# old_main_board.net
KiCad netlist of a schematic drawn in EAGLE
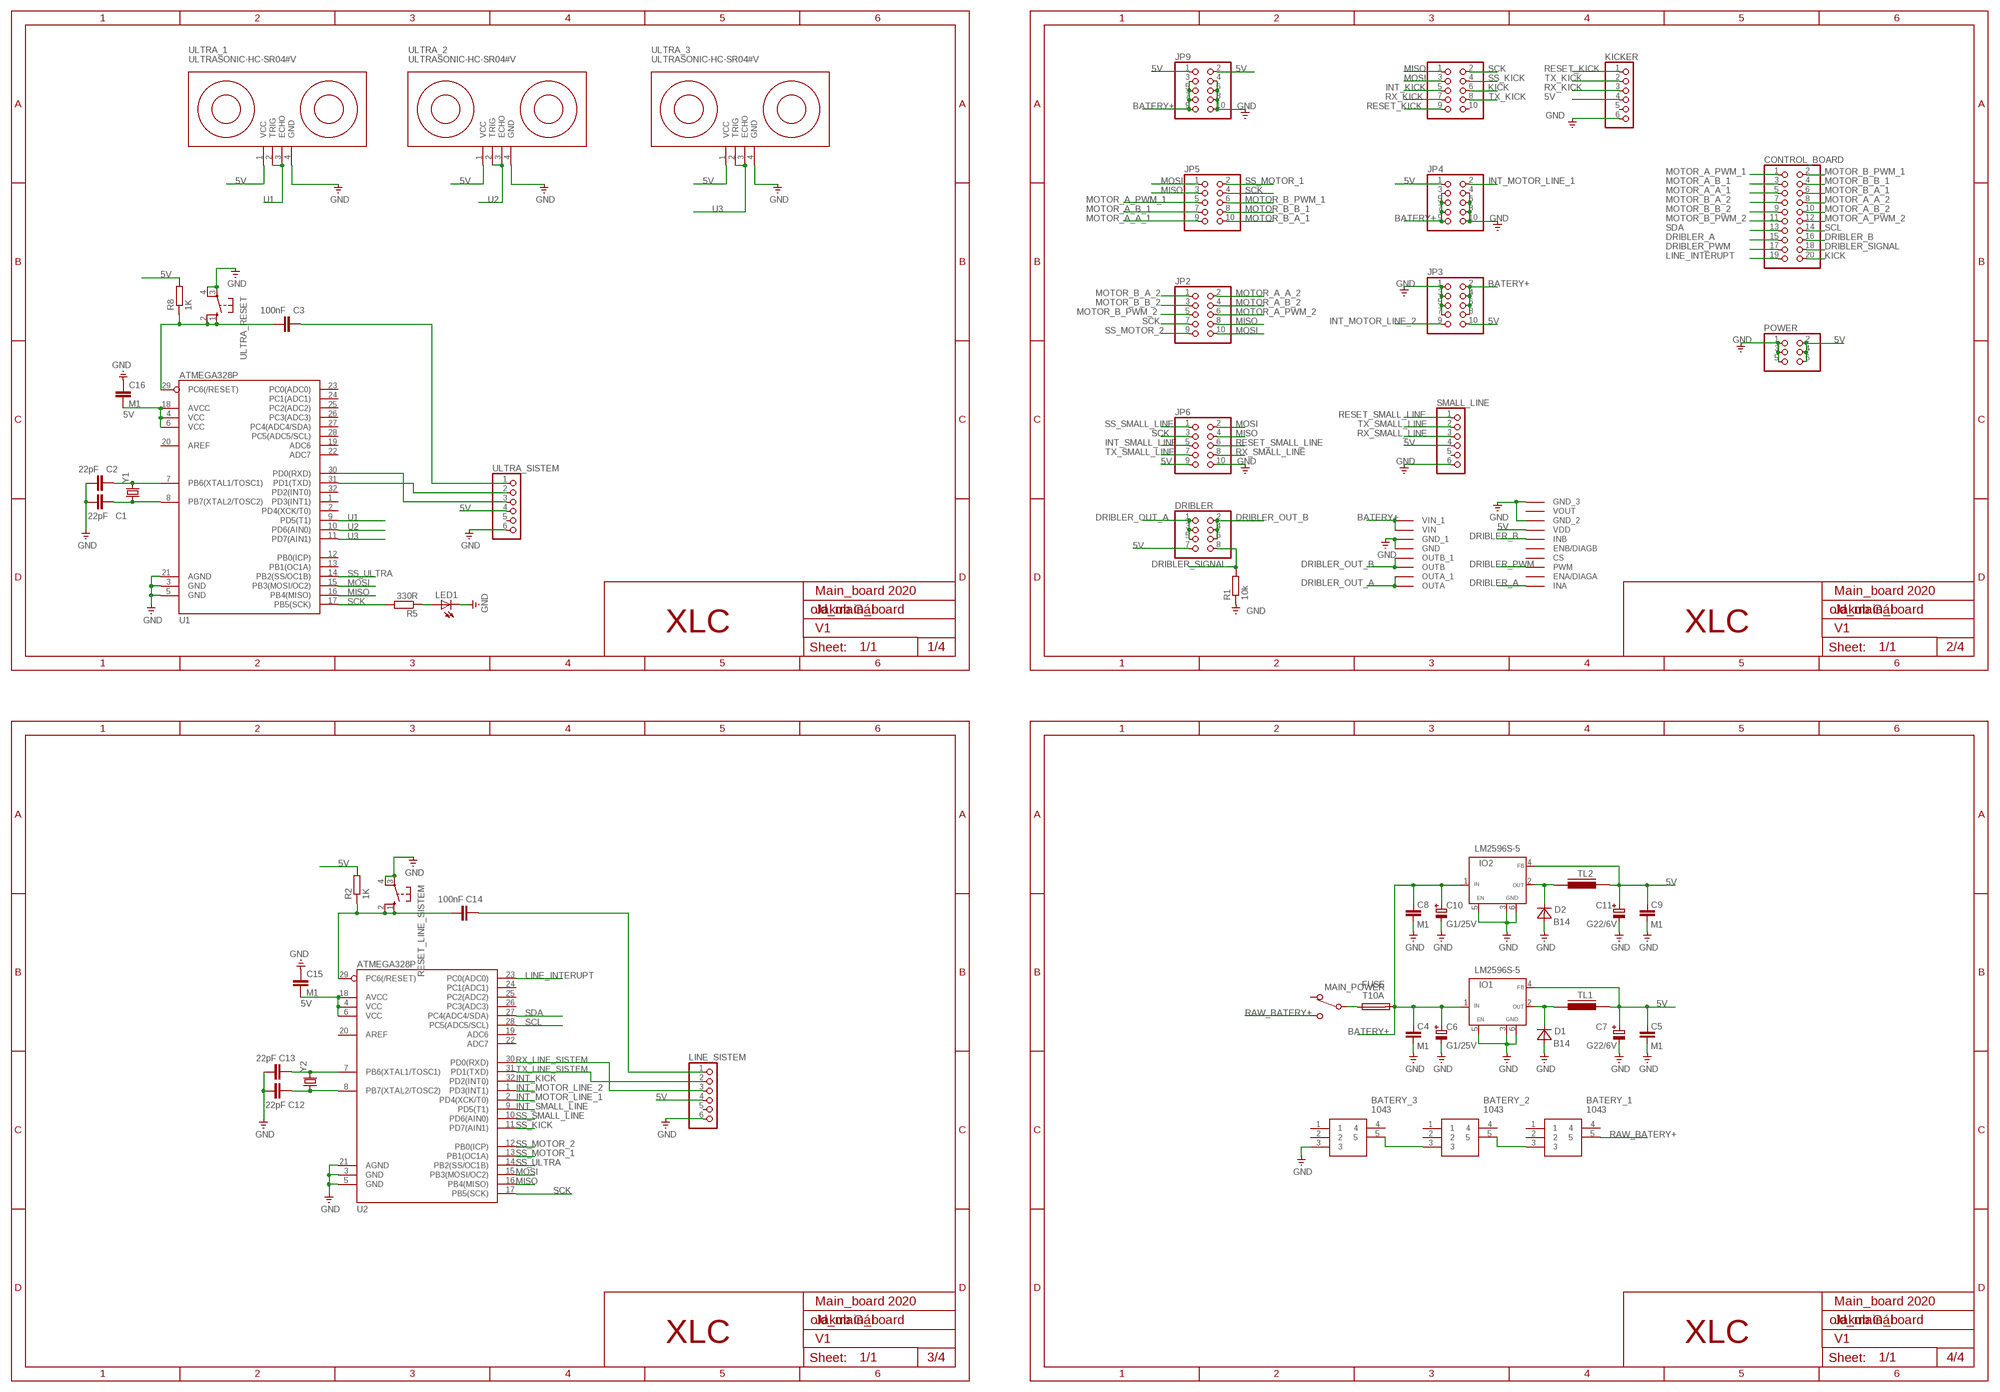
[diagram p0: schematic, sheet 1]

(export (version "E")
  (design (tool "Eeschema 10.0.6"))
  (components
    (comp (ref "BATERY_1")
      (value "1043")
      (footprint "eagle-import:1043")
      (fields (field (name "MOUSER_PART_NUMBER") "534-1043"))
      (libsource (lib "eagle-import") (part "1043"))
    )
    (comp (ref "BATERY_2")
      (value "1043")
      (footprint "eagle-import:1043")
      (fields (field (name "MOUSER_PART_NUMBER") "534-1043"))
      (libsource (lib "eagle-import") (part "1043"))
    )
    (comp (ref "BATERY_3")
      (value "1043")
      (footprint "eagle-import:1043")
      (fields (field (name "MOUSER_PART_NUMBER") "534-1043"))
      (libsource (lib "eagle-import") (part "1043"))
    )
    (comp (ref "C1")
      (value "22pF")
      (footprint "eagle-import:C0603")
      (libsource (lib "eagle-import") (part "rcl@1_C-EUC0603"))
    )
    (comp (ref "C2")
      (value "22pF")
      (footprint "eagle-import:C0603")
      (libsource (lib "eagle-import") (part "rcl@1_C-EUC0603"))
    )
    (comp (ref "C3")
      (value "100nF")
      (footprint "eagle-import:C0603")
      (libsource (lib "eagle-import") (part "rcl@1_C-EUC0603"))
    )
    (comp (ref "C4")
      (value "M1")
      (footprint "eagle-import:SMD-1206")
      (libsource (lib "eagle-import") (part "KOND-KERAM1206-SMD"))
    )
    (comp (ref "C5")
      (value "M1")
      (footprint "eagle-import:SMD-1206")
      (libsource (lib "eagle-import") (part "KOND-KERAM1206-SMD"))
    )
    (comp (ref "C6")
      (value "G1/25V")
      (footprint "eagle-import:SMD-ELE-D")
      (libsource (lib "eagle-import") (part "KOND-ELEKTD-SMD"))
    )
    (comp (ref "C7")
      (value "G22/6V")
      (footprint "eagle-import:SMD-ELE-D")
      (libsource (lib "eagle-import") (part "KOND-ELEKTD-SMD"))
    )
    (comp (ref "C8")
      (value "M1")
      (footprint "eagle-import:SMD-1206")
      (libsource (lib "eagle-import") (part "KOND-KERAM1206-SMD"))
    )
    (comp (ref "C9")
      (value "M1")
      (footprint "eagle-import:SMD-1206")
      (libsource (lib "eagle-import") (part "KOND-KERAM1206-SMD"))
    )
    (comp (ref "C10")
      (value "G1/25V")
      (footprint "eagle-import:SMD-ELE-D")
      (libsource (lib "eagle-import") (part "KOND-ELEKTD-SMD"))
    )
    (comp (ref "C11")
      (value "G22/6V")
      (footprint "eagle-import:SMD-ELE-D")
      (libsource (lib "eagle-import") (part "KOND-ELEKTD-SMD"))
    )
    (comp (ref "C12")
      (value "22pF")
      (footprint "eagle-import:C0603")
      (libsource (lib "eagle-import") (part "rcl@1_C-EUC0603"))
    )
    (comp (ref "C13")
      (value "22pF")
      (footprint "eagle-import:C0603")
      (libsource (lib "eagle-import") (part "rcl@1_C-EUC0603"))
    )
    (comp (ref "C14")
      (value "100nF")
      (footprint "eagle-import:C0603")
      (libsource (lib "eagle-import") (part "rcl@1_C-EUC0603"))
    )
    (comp (ref "C15")
      (value "M1")
      (footprint "eagle-import:C0603")
      (libsource (lib "eagle-import") (part "C-EUC0603"))
    )
    (comp (ref "C16")
      (value "M1")
      (footprint "eagle-import:C0603")
      (libsource (lib "eagle-import") (part "C-EUC0603"))
    )
    (comp (ref "CONTROL_BOARD")
      (value "PINHD-2X10_2.54-SMD")
      (footprint "eagle-import:2X10SMD")
      (libsource (lib "eagle-import") (part "PINHD-2X10_2.54-SMD"))
    )
    (comp (ref "D1")
      (value "B14")
      (footprint "eagle-import:D-3,6X5,5")
      (libsource (lib "eagle-import") (part "DIODASMD-3,6X5,5"))
    )
    (comp (ref "D2")
      (value "B14")
      (footprint "eagle-import:D-3,6X5,5")
      (libsource (lib "eagle-import") (part "DIODASMD-3,6X5,5"))
    )
    (comp (ref "DRIBLER")
      (value "PINHD-2X4_2.54-SMD")
      (footprint "eagle-import:2X04SMD")
      (libsource (lib "eagle-import") (part "PINHD-2X4_2.54-SMD"))
    )
    (comp (ref "FUSE")
      (value "T10A")
      (footprint "eagle-import:SH22,5A")
      (libsource (lib "eagle-import") (part "POISTKA2A"))
    )
    (comp (ref "IO1")
      (value "LM2596S-5")
      (footprint "eagle-import:TO263-5")
      (libsource (lib "eagle-import") (part "LM2596S"))
    )
    (comp (ref "IO2")
      (value "LM2596S-5")
      (footprint "eagle-import:TO263-5")
      (libsource (lib "eagle-import") (part "LM2596S"))
    )
    (comp (ref "JP2")
      (value "PINHD-2X5_2.54-SMD")
      (footprint "eagle-import:2X05SMD")
      (libsource (lib "eagle-import") (part "PINHD-2X5_2.54-SMD"))
    )
    (comp (ref "JP3")
      (value "PINHD-2X5_2.54-SMD")
      (footprint "eagle-import:2X05SMD")
      (libsource (lib "eagle-import") (part "PINHD-2X5_2.54-SMD"))
    )
    (comp (ref "JP4")
      (value "PINHD-2X5_2.54-SMD")
      (footprint "eagle-import:2X05SMD")
      (libsource (lib "eagle-import") (part "PINHD-2X5_2.54-SMD"))
    )
    (comp (ref "JP5")
      (value "PINHD-2X5_2.54-SMD")
      (footprint "eagle-import:2X05SMD")
      (libsource (lib "eagle-import") (part "PINHD-2X5_2.54-SMD"))
    )
    (comp (ref "JP6")
      (value "PINHD-2X5_2.54-SMD")
      (footprint "eagle-import:2X05SMD")
      (libsource (lib "eagle-import") (part "PINHD-2X5_2.54-SMD"))
    )
    (comp (ref "JP8")
      (value "PINHD-2X5_2.54-SMD")
      (footprint "eagle-import:2X05SMD")
      (libsource (lib "eagle-import") (part "PINHD-2X5_2.54-SMD"))
    )
    (comp (ref "JP9")
      (value "PINHD-2X5_2.54-SMD")
      (footprint "eagle-import:2X05SMD")
      (libsource (lib "eagle-import") (part "PINHD-2X5_2.54-SMD"))
    )
    (comp (ref "KICKER")
      (value "PINHD-1X6")
      (footprint "eagle-import:1X06")
      (libsource (lib "eagle-import") (part "PINHD-1X6"))
    )
    (comp (ref "LED1")
      (value "LEDCHIPLED_0603")
      (footprint "eagle-import:CHIPLED_0603")
      (libsource (lib "eagle-import") (part "LEDCHIPLED_0603"))
    )
    (comp (ref "LINE_SISTEM")
      (value "PINHD-1X6")
      (footprint "eagle-import:1X06")
      (libsource (lib "eagle-import") (part "PINHD-1X6"))
    )
    (comp (ref "MAIN_POWER")
      (value "PREP-1PB")
      (footprint "eagle-import:P-B069B")
      (libsource (lib "eagle-import") (part "PREP-1PB"))
    )
    (comp (ref "POWER")
      (value "PINHD-2X3_2.54-SMD")
      (footprint "eagle-import:2X03SMD")
      (libsource (lib "eagle-import") (part "PINHD-2X3_2.54-SMD"))
    )
    (comp (ref "R1")
      (value "10k")
      (footprint "eagle-import:R0603")
      (libsource (lib "eagle-import") (part "R-EU_R0603"))
    )
    (comp (ref "R2")
      (value "1K")
      (footprint "eagle-import:R0603")
      (libsource (lib "eagle-import") (part "R-EU_R0603"))
    )
    (comp (ref "R5")
      (value "330R")
      (footprint "eagle-import:R0603")
      (libsource (lib "eagle-import") (part "R-EU_R0603"))
    )
    (comp (ref "R8")
      (value "1K")
      (footprint "eagle-import:R0603")
      (libsource (lib "eagle-import") (part "R-EU_R0603"))
    )
    (comp (ref "RESET_LINE_SISTEM")
      (value "10-XX")
      (footprint "eagle-import:B3F-10XX")
      (fields (field (name "MPN") "B3F-1000"))
      (libsource (lib "eagle-import") (part "10-XX"))
    )
    (comp (ref "SMALL_LINE")
      (value "PINHD-1X6")
      (footprint "eagle-import:1X06")
      (libsource (lib "eagle-import") (part "PINHD-1X6"))
    )
    (comp (ref "TL1")
      (value "INDUK-TLSMD1")
      (footprint "eagle-import:INDUK-TL")
      (libsource (lib "eagle-import") (part "INDUK-TLSMD1"))
    )
    (comp (ref "TL2")
      (value "INDUK-TLSMD1")
      (footprint "eagle-import:INDUK-TL")
      (libsource (lib "eagle-import") (part "INDUK-TLSMD1"))
    )
    (comp (ref "U$4")
      (value "MOTOR_DRIVER")
      (footprint "eagle-import:MOTOR_DRIVER")
      (libsource (lib "eagle-import") (part "MOTOR_DRIVER"))
    )
    (comp (ref "U1")
      (value "ATMEGA328P")
      (footprint "eagle-import:TQFP32-08")
      (libsource (lib "eagle-import") (part "ATMEGA328_SMT"))
    )
    (comp (ref "U2")
      (value "ATMEGA328P")
      (footprint "eagle-import:TQFP32-08")
      (libsource (lib "eagle-import") (part "ATMEGA328_SMT"))
    )
    (comp (ref "ULTRA_1")
      (value "ULTRASONIC-HC-SR04#V")
      (footprint "eagle-import:ULTRASONIC-HC-SR04#V")
      (libsource (lib "eagle-import") (part "ULTRASONIC-HC-SR04#V"))
    )
    (comp (ref "ULTRA_2")
      (value "ULTRASONIC-HC-SR04#V")
      (footprint "eagle-import:ULTRASONIC-HC-SR04#V")
      (libsource (lib "eagle-import") (part "ULTRASONIC-HC-SR04#V"))
    )
    (comp (ref "ULTRA_3")
      (value "ULTRASONIC-HC-SR04#V")
      (footprint "eagle-import:ULTRASONIC-HC-SR04#V")
      (libsource (lib "eagle-import") (part "ULTRASONIC-HC-SR04#V"))
    )
    (comp (ref "ULTRA_RESET")
      (value "10-XX")
      (footprint "eagle-import:B3F-10XX")
      (fields (field (name "MPN") "B3F-1000"))
      (libsource (lib "eagle-import") (part "10-XX"))
    )
    (comp (ref "ULTRA_SISTEM")
      (value "PINHD-1X6")
      (footprint "eagle-import:1X06")
      (libsource (lib "eagle-import") (part "PINHD-1X6"))
    )
    (comp (ref "Y1")
      (value "CRYSTALHC49US")
      (footprint "eagle-import:HC49US")
      (libsource (lib "eagle-import") (part "CRYSTALHC49US"))
    )
    (comp (ref "Y2")
      (value "CRYSTALHC49US")
      (footprint "eagle-import:HC49US")
      (libsource (lib "eagle-import") (part "CRYSTALHC49US"))
    )
  )
  (nets
    (net (code "1") (name "/5V") (class "Default")
      (node (ref "C11") (pin "PLUS") (pinfunction "PLUS_PLUS") (pintype "passive"))
      (node (ref "C15") (pin "2") (pinfunction "2_2") (pintype "passive"))
      (node (ref "C16") (pin "2") (pinfunction "2_2") (pintype "passive"))
      (node (ref "C5") (pin "2") (pinfunction "2_2") (pintype "passive"))
      (node (ref "C7") (pin "PLUS") (pinfunction "PLUS_PLUS") (pintype "passive"))
      (node (ref "C9") (pin "2") (pinfunction "2_2") (pintype "passive"))
      (node (ref "DRIBLER") (pin "7") (pinfunction "7_7") (pintype "passive"))
      (node (ref "IO1") (pin "4") (pinfunction "FB_4") (pintype "input"))
      (node (ref "IO2") (pin "4") (pinfunction "FB_4") (pintype "input"))
      (node (ref "JP3") (pin "10") (pinfunction "10_10") (pintype "passive"))
      (node (ref "JP4") (pin "1") (pinfunction "1_1") (pintype "passive"))
      (node (ref "JP6") (pin "9") (pinfunction "9_9") (pintype "passive"))
      (node (ref "JP9") (pin "1") (pinfunction "1_1") (pintype "passive"))
      (node (ref "JP9") (pin "2") (pinfunction "2_2") (pintype "passive"))
      (node (ref "KICKER") (pin "4") (pinfunction "4_4") (pintype "passive"))
      (node (ref "LINE_SISTEM") (pin "4") (pinfunction "4_4") (pintype "passive"))
      (node (ref "POWER") (pin "2") (pinfunction "2_2") (pintype "passive"))
      (node (ref "POWER") (pin "4") (pinfunction "4_4") (pintype "passive"))
      (node (ref "POWER") (pin "6") (pinfunction "6_6") (pintype "passive"))
      (node (ref "R2") (pin "2") (pinfunction "2_2") (pintype "passive"))
      (node (ref "R8") (pin "2") (pinfunction "2_2") (pintype "passive"))
      (node (ref "SMALL_LINE") (pin "4") (pinfunction "4_4") (pintype "passive"))
      (node (ref "TL1") (pin "2") (pinfunction "2_2") (pintype "passive"))
      (node (ref "TL2") (pin "2") (pinfunction "2_2") (pintype "passive"))
      (node (ref "U$4") (pin "VDD") (pinfunction "VDD_VDD") (pintype "bidirectional"))
      (node (ref "U1") (pin "18") (pinfunction "AVCC_18") (pintype "bidirectional"))
      (node (ref "U1") (pin "4") (pinfunction "VCC_4") (pintype "bidirectional"))
      (node (ref "U1") (pin "6") (pinfunction "VCC_6") (pintype "bidirectional"))
      (node (ref "U2") (pin "18") (pinfunction "AVCC_18") (pintype "bidirectional"))
      (node (ref "U2") (pin "4") (pinfunction "VCC_4") (pintype "bidirectional"))
      (node (ref "U2") (pin "6") (pinfunction "VCC_6") (pintype "bidirectional"))
      (node (ref "ULTRA_1") (pin "1") (pinfunction "VCC_1") (pintype "power_in"))
      (node (ref "ULTRA_2") (pin "1") (pinfunction "VCC_1") (pintype "power_in"))
      (node (ref "ULTRA_3") (pin "1") (pinfunction "VCC_1") (pintype "power_in"))
      (node (ref "ULTRA_SISTEM") (pin "4") (pinfunction "4_4") (pintype "passive"))
    )
    (net (code "2") (name "/BATERY+") (class "Default")
      (node (ref "C10") (pin "PLUS") (pinfunction "PLUS_PLUS") (pintype "passive"))
      (node (ref "C4") (pin "2") (pinfunction "2_2") (pintype "passive"))
      (node (ref "C6") (pin "PLUS") (pinfunction "PLUS_PLUS") (pintype "passive"))
      (node (ref "C8") (pin "2") (pinfunction "2_2") (pintype "passive"))
      (node (ref "FUSE") (pin "2") (pinfunction "2_2") (pintype "passive"))
      (node (ref "IO1") (pin "1") (pinfunction "IN_1") (pintype "input"))
      (node (ref "IO2") (pin "1") (pinfunction "IN_1") (pintype "input"))
      (node (ref "JP3") (pin "2") (pinfunction "2_2") (pintype "passive"))
      (node (ref "JP3") (pin "4") (pinfunction "4_4") (pintype "passive"))
      (node (ref "JP3") (pin "6") (pinfunction "6_6") (pintype "passive"))
      (node (ref "JP3") (pin "8") (pinfunction "8_8") (pintype "passive"))
      (node (ref "JP4") (pin "3") (pinfunction "3_3") (pintype "passive"))
      (node (ref "JP4") (pin "5") (pinfunction "5_5") (pintype "passive"))
      (node (ref "JP4") (pin "7") (pinfunction "7_7") (pintype "passive"))
      (node (ref "JP4") (pin "9") (pinfunction "9_9") (pintype "passive"))
      (node (ref "JP9") (pin "3") (pinfunction "3_3") (pintype "passive"))
      (node (ref "JP9") (pin "5") (pinfunction "5_5") (pintype "passive"))
      (node (ref "JP9") (pin "7") (pinfunction "7_7") (pintype "passive"))
      (node (ref "JP9") (pin "9") (pinfunction "9_9") (pintype "passive"))
      (node (ref "U$4") (pin "VIN") (pinfunction "VIN_VIN") (pintype "bidirectional"))
      (node (ref "U$4") (pin "VIN_1") (pinfunction "VIN_1_VIN_1") (pintype "bidirectional"))
    )
    (net (code "3") (name "/DRIBLER_A") (class "Default")
      (node (ref "CONTROL_BOARD") (pin "15") (pinfunction "15_15") (pintype "passive"))
      (node (ref "U$4") (pin "INA") (pinfunction "INA_INA") (pintype "bidirectional"))
    )
    (net (code "4") (name "/DRIBLER_B") (class "Default")
      (node (ref "CONTROL_BOARD") (pin "16") (pinfunction "16_16") (pintype "passive"))
      (node (ref "U$4") (pin "INB") (pinfunction "INB_INB") (pintype "bidirectional"))
    )
    (net (code "5") (name "/DRIBLER_OUT_A") (class "Default")
      (node (ref "DRIBLER") (pin "1") (pinfunction "1_1") (pintype "passive"))
      (node (ref "DRIBLER") (pin "3") (pinfunction "3_3") (pintype "passive"))
      (node (ref "DRIBLER") (pin "5") (pinfunction "5_5") (pintype "passive"))
      (node (ref "U$4") (pin "OUTA") (pinfunction "OUTA_OUTA") (pintype "bidirectional"))
      (node (ref "U$4") (pin "OUTA_1") (pinfunction "OUTA_1_OUTA_1") (pintype "bidirectional"))
    )
    (net (code "6") (name "/DRIBLER_OUT_B") (class "Default")
      (node (ref "DRIBLER") (pin "2") (pinfunction "2_2") (pintype "passive"))
      (node (ref "DRIBLER") (pin "4") (pinfunction "4_4") (pintype "passive"))
      (node (ref "DRIBLER") (pin "6") (pinfunction "6_6") (pintype "passive"))
      (node (ref "U$4") (pin "OUTB") (pinfunction "OUTB_OUTB") (pintype "bidirectional"))
      (node (ref "U$4") (pin "OUTB_1") (pinfunction "OUTB_1_OUTB_1") (pintype "bidirectional"))
    )
    (net (code "7") (name "/DRIBLER_PWM") (class "Default")
      (node (ref "CONTROL_BOARD") (pin "17") (pinfunction "17_17") (pintype "passive"))
      (node (ref "U$4") (pin "PWM") (pinfunction "PWM_PWM") (pintype "bidirectional"))
    )
    (net (code "8") (name "/DRIBLER_SIGNAL") (class "Default")
      (node (ref "CONTROL_BOARD") (pin "18") (pinfunction "18_18") (pintype "passive"))
      (node (ref "DRIBLER") (pin "8") (pinfunction "8_8") (pintype "passive"))
      (node (ref "R1") (pin "2") (pinfunction "2_2") (pintype "passive"))
    )
    (net (code "9") (name "/INT_KICK") (class "Default")
      (node (ref "JP8") (pin "5") (pinfunction "5_5") (pintype "passive"))
      (node (ref "U2") (pin "32") (pinfunction "PD2(INT0)_32") (pintype "bidirectional"))
    )
    (net (code "10") (name "/INT_MOTOR_LINE_1") (class "Default")
      (node (ref "JP4") (pin "2") (pinfunction "2_2") (pintype "passive"))
      (node (ref "U2") (pin "2") (pinfunction "PD4(XCK/T0)_2") (pintype "bidirectional"))
    )
    (net (code "11") (name "/INT_MOTOR_LINE_2") (class "Default")
      (node (ref "JP3") (pin "9") (pinfunction "9_9") (pintype "passive"))
      (node (ref "U2") (pin "1") (pinfunction "PD3(INT1)_1") (pintype "bidirectional"))
    )
    (net (code "12") (name "/INT_SMALL_LINE") (class "Default")
      (node (ref "JP6") (pin "5") (pinfunction "5_5") (pintype "passive"))
      (node (ref "U2") (pin "9") (pinfunction "PD5(T1)_9") (pintype "bidirectional"))
    )
    (net (code "13") (name "/KICK") (class "Default")
      (node (ref "CONTROL_BOARD") (pin "20") (pinfunction "20_20") (pintype "passive"))
      (node (ref "JP8") (pin "6") (pinfunction "6_6") (pintype "passive"))
    )
    (net (code "14") (name "/LINE_INTERUPT") (class "Default")
      (node (ref "CONTROL_BOARD") (pin "19") (pinfunction "19_19") (pintype "passive"))
      (node (ref "U2") (pin "23") (pinfunction "PC0(ADC0)_23") (pintype "bidirectional"))
    )
    (net (code "15") (name "/MISO") (class "Default")
      (node (ref "JP2") (pin "8") (pinfunction "8_8") (pintype "passive"))
      (node (ref "JP5") (pin "3") (pinfunction "3_3") (pintype "passive"))
      (node (ref "JP6") (pin "4") (pinfunction "4_4") (pintype "passive"))
      (node (ref "JP8") (pin "1") (pinfunction "1_1") (pintype "passive"))
      (node (ref "U1") (pin "16") (pinfunction "PB4(MISO)_16") (pintype "bidirectional"))
      (node (ref "U2") (pin "16") (pinfunction "PB4(MISO)_16") (pintype "bidirectional"))
    )
    (net (code "16") (name "/MOSI") (class "Default")
      (node (ref "JP2") (pin "10") (pinfunction "10_10") (pintype "passive"))
      (node (ref "JP5") (pin "1") (pinfunction "1_1") (pintype "passive"))
      (node (ref "JP6") (pin "2") (pinfunction "2_2") (pintype "passive"))
      (node (ref "JP8") (pin "3") (pinfunction "3_3") (pintype "passive"))
      (node (ref "U1") (pin "15") (pinfunction "PB3(MOSI/OC2)_15") (pintype "bidirectional"))
      (node (ref "U2") (pin "15") (pinfunction "PB3(MOSI/OC2)_15") (pintype "bidirectional"))
    )
    (net (code "17") (name "/MOTOR_A_A_1") (class "Default")
      (node (ref "CONTROL_BOARD") (pin "5") (pinfunction "5_5") (pintype "passive"))
      (node (ref "JP5") (pin "9") (pinfunction "9_9") (pintype "passive"))
    )
    (net (code "18") (name "/MOTOR_A_A_2") (class "Default")
      (node (ref "CONTROL_BOARD") (pin "8") (pinfunction "8_8") (pintype "passive"))
      (node (ref "JP2") (pin "2") (pinfunction "2_2") (pintype "passive"))
    )
    (net (code "19") (name "/MOTOR_A_B_1") (class "Default")
      (node (ref "CONTROL_BOARD") (pin "3") (pinfunction "3_3") (pintype "passive"))
      (node (ref "JP5") (pin "7") (pinfunction "7_7") (pintype "passive"))
    )
    (net (code "20") (name "/MOTOR_A_B_2") (class "Default")
      (node (ref "CONTROL_BOARD") (pin "10") (pinfunction "10_10") (pintype "passive"))
      (node (ref "JP2") (pin "4") (pinfunction "4_4") (pintype "passive"))
    )
    (net (code "21") (name "/MOTOR_A_PWM_1") (class "Default")
      (node (ref "CONTROL_BOARD") (pin "1") (pinfunction "1_1") (pintype "passive"))
      (node (ref "JP5") (pin "5") (pinfunction "5_5") (pintype "passive"))
    )
    (net (code "22") (name "/MOTOR_A_PWM_2") (class "Default")
      (node (ref "CONTROL_BOARD") (pin "12") (pinfunction "12_12") (pintype "passive"))
      (node (ref "JP2") (pin "6") (pinfunction "6_6") (pintype "passive"))
    )
    (net (code "23") (name "/MOTOR_B_A_1") (class "Default")
      (node (ref "CONTROL_BOARD") (pin "6") (pinfunction "6_6") (pintype "passive"))
      (node (ref "JP5") (pin "10") (pinfunction "10_10") (pintype "passive"))
    )
    (net (code "24") (name "/MOTOR_B_A_2") (class "Default")
      (node (ref "CONTROL_BOARD") (pin "7") (pinfunction "7_7") (pintype "passive"))
      (node (ref "JP2") (pin "1") (pinfunction "1_1") (pintype "passive"))
    )
    (net (code "25") (name "/MOTOR_B_B_1") (class "Default")
      (node (ref "CONTROL_BOARD") (pin "4") (pinfunction "4_4") (pintype "passive"))
      (node (ref "JP5") (pin "8") (pinfunction "8_8") (pintype "passive"))
    )
    (net (code "26") (name "/MOTOR_B_B_2") (class "Default")
      (node (ref "CONTROL_BOARD") (pin "9") (pinfunction "9_9") (pintype "passive"))
      (node (ref "JP2") (pin "3") (pinfunction "3_3") (pintype "passive"))
    )
    (net (code "27") (name "/MOTOR_B_PWM_1") (class "Default")
      (node (ref "CONTROL_BOARD") (pin "2") (pinfunction "2_2") (pintype "passive"))
      (node (ref "JP5") (pin "6") (pinfunction "6_6") (pintype "passive"))
    )
    (net (code "28") (name "/MOTOR_B_PWM_2") (class "Default")
      (node (ref "CONTROL_BOARD") (pin "11") (pinfunction "11_11") (pintype "passive"))
      (node (ref "JP2") (pin "5") (pinfunction "5_5") (pintype "passive"))
    )
    (net (code "29") (name "/RAW_BATERY+") (class "Default")
      (node (ref "BATERY_1") (pin "5") (pinfunction "5_5") (pintype "bidirectional"))
      (node (ref "MAIN_POWER") (pin "1") (pinfunction "1-OFF_1") (pintype "passive"))
    )
    (net (code "30") (name "/RESET_KICK") (class "Default")
      (node (ref "JP8") (pin "9") (pinfunction "9_9") (pintype "passive"))
      (node (ref "KICKER") (pin "1") (pinfunction "1_1") (pintype "passive"))
    )
    (net (code "31") (name "/RESET_SMALL_LINE") (class "Default")
      (node (ref "JP6") (pin "6") (pinfunction "6_6") (pintype "passive"))
      (node (ref "SMALL_LINE") (pin "1") (pinfunction "1_1") (pintype "passive"))
    )
    (net (code "32") (name "/RX_KICK") (class "Default")
      (node (ref "JP8") (pin "7") (pinfunction "7_7") (pintype "passive"))
      (node (ref "KICKER") (pin "3") (pinfunction "3_3") (pintype "passive"))
    )
    (net (code "33") (name "/RX_LINE_SISTEM") (class "Default")
      (node (ref "LINE_SISTEM") (pin "3") (pinfunction "3_3") (pintype "passive"))
      (node (ref "U2") (pin "30") (pinfunction "PD0(RXD)_30") (pintype "bidirectional"))
    )
    (net (code "34") (name "/RX_SMALL_LINE") (class "Default")
      (node (ref "JP6") (pin "8") (pinfunction "8_8") (pintype "passive"))
      (node (ref "SMALL_LINE") (pin "3") (pinfunction "3_3") (pintype "passive"))
    )
    (net (code "35") (name "/SCK") (class "Default")
      (node (ref "JP2") (pin "7") (pinfunction "7_7") (pintype "passive"))
      (node (ref "JP5") (pin "4") (pinfunction "4_4") (pintype "passive"))
      (node (ref "JP6") (pin "3") (pinfunction "3_3") (pintype "passive"))
      (node (ref "JP8") (pin "2") (pinfunction "2_2") (pintype "passive"))
      (node (ref "R5") (pin "2") (pinfunction "2_2") (pintype "passive"))
      (node (ref "U1") (pin "17") (pinfunction "PB5(SCK)_17") (pintype "bidirectional"))
      (node (ref "U2") (pin "17") (pinfunction "PB5(SCK)_17") (pintype "bidirectional"))
    )
    (net (code "36") (name "/SCL") (class "Default")
      (node (ref "CONTROL_BOARD") (pin "14") (pinfunction "14_14") (pintype "passive"))
      (node (ref "U2") (pin "28") (pinfunction "PC5(ADC5/SCL)_28") (pintype "bidirectional"))
    )
    (net (code "37") (name "/SDA") (class "Default")
      (node (ref "CONTROL_BOARD") (pin "13") (pinfunction "13_13") (pintype "passive"))
      (node (ref "U2") (pin "27") (pinfunction "PC4(ADC4/SDA)_27") (pintype "bidirectional"))
    )
    (net (code "38") (name "/SS_KICK") (class "Default")
      (node (ref "JP8") (pin "4") (pinfunction "4_4") (pintype "passive"))
      (node (ref "U2") (pin "11") (pinfunction "PD7(AIN1)_11") (pintype "bidirectional"))
    )
    (net (code "39") (name "/SS_MOTOR_1") (class "Default")
      (node (ref "JP5") (pin "2") (pinfunction "2_2") (pintype "passive"))
      (node (ref "U2") (pin "13") (pinfunction "PB1(OC1A)_13") (pintype "bidirectional"))
    )
    (net (code "40") (name "/SS_MOTOR_2") (class "Default")
      (node (ref "JP2") (pin "9") (pinfunction "9_9") (pintype "passive"))
      (node (ref "U2") (pin "12") (pinfunction "PB0(ICP)_12") (pintype "bidirectional"))
    )
    (net (code "41") (name "/SS_SMALL_LINE") (class "Default")
      (node (ref "JP6") (pin "1") (pinfunction "1_1") (pintype "passive"))
      (node (ref "U2") (pin "10") (pinfunction "PD6(AIN0)_10") (pintype "bidirectional"))
    )
    (net (code "42") (name "/SS_ULTRA") (class "Default")
      (node (ref "U1") (pin "14") (pinfunction "PB2(SS/OC1B)_14") (pintype "bidirectional"))
      (node (ref "U2") (pin "14") (pinfunction "PB2(SS/OC1B)_14") (pintype "bidirectional"))
    )
    (net (code "43") (name "/TX_KICK") (class "Default")
      (node (ref "JP8") (pin "8") (pinfunction "8_8") (pintype "passive"))
      (node (ref "KICKER") (pin "2") (pinfunction "2_2") (pintype "passive"))
    )
    (net (code "44") (name "/TX_LINE_SISTEM") (class "Default")
      (node (ref "LINE_SISTEM") (pin "2") (pinfunction "2_2") (pintype "passive"))
      (node (ref "U2") (pin "31") (pinfunction "PD1(TXD)_31") (pintype "bidirectional"))
    )
    (net (code "45") (name "/TX_SMALL_LINE") (class "Default")
      (node (ref "JP6") (pin "7") (pinfunction "7_7") (pintype "passive"))
      (node (ref "SMALL_LINE") (pin "2") (pinfunction "2_2") (pintype "passive"))
    )
    (net (code "46") (name "/U1") (class "Default")
      (node (ref "U1") (pin "9") (pinfunction "PD5(T1)_9") (pintype "bidirectional"))
      (node (ref "ULTRA_1") (pin "2") (pinfunction "TRIG_2") (pintype "input"))
      (node (ref "ULTRA_1") (pin "3") (pinfunction "ECHO_3") (pintype "output"))
    )
    (net (code "47") (name "/U2") (class "Default")
      (node (ref "U1") (pin "10") (pinfunction "PD6(AIN0)_10") (pintype "bidirectional"))
      (node (ref "ULTRA_2") (pin "2") (pinfunction "TRIG_2") (pintype "input"))
      (node (ref "ULTRA_2") (pin "3") (pinfunction "ECHO_3") (pintype "output"))
    )
    (net (code "48") (name "/U3") (class "Default")
      (node (ref "U1") (pin "11") (pinfunction "PD7(AIN1)_11") (pintype "bidirectional"))
      (node (ref "ULTRA_3") (pin "2") (pinfunction "TRIG_2") (pintype "input"))
      (node (ref "ULTRA_3") (pin "3") (pinfunction "ECHO_3") (pintype "output"))
    )
    (net (code "49") (name "GND") (class "Default")
      (node (ref "BATERY_3") (pin "3") (pinfunction "3_3") (pintype "bidirectional"))
      (node (ref "C1") (pin "1") (pinfunction "1_1") (pintype "passive"))
      (node (ref "C10") (pin "MINUS") (pinfunction "MINUS_MINUS") (pintype "passive"))
      (node (ref "C11") (pin "MINUS") (pinfunction "MINUS_MINUS") (pintype "passive"))
      (node (ref "C12") (pin "1") (pinfunction "1_1") (pintype "passive"))
      (node (ref "C13") (pin "1") (pinfunction "1_1") (pintype "passive"))
      (node (ref "C15") (pin "1") (pinfunction "1_1") (pintype "passive"))
      (node (ref "C16") (pin "1") (pinfunction "1_1") (pintype "passive"))
      (node (ref "C2") (pin "1") (pinfunction "1_1") (pintype "passive"))
      (node (ref "C4") (pin "1") (pinfunction "1_1") (pintype "passive"))
      (node (ref "C5") (pin "1") (pinfunction "1_1") (pintype "passive"))
      (node (ref "C6") (pin "MINUS") (pinfunction "MINUS_MINUS") (pintype "passive"))
      (node (ref "C7") (pin "MINUS") (pinfunction "MINUS_MINUS") (pintype "passive"))
      (node (ref "C8") (pin "1") (pinfunction "1_1") (pintype "passive"))
      (node (ref "C9") (pin "1") (pinfunction "1_1") (pintype "passive"))
      (node (ref "D1") (pin "A") (pinfunction "A_A") (pintype "passive"))
      (node (ref "D2") (pin "A") (pinfunction "A_A") (pintype "passive"))
      (node (ref "IO1") (pin "3") (pinfunction "GND_3") (pintype "power_in"))
      (node (ref "IO1") (pin "5") (pinfunction "EN_5") (pintype "input"))
      (node (ref "IO1") (pin "6") (pinfunction "GND_6") (pintype "power_in"))
      (node (ref "IO2") (pin "3") (pinfunction "GND_3") (pintype "power_in"))
      (node (ref "IO2") (pin "5") (pinfunction "EN_5") (pintype "input"))
      (node (ref "IO2") (pin "6") (pinfunction "GND_6") (pintype "power_in"))
      (node (ref "JP3") (pin "1") (pinfunction "1_1") (pintype "passive"))
      (node (ref "JP3") (pin "3") (pinfunction "3_3") (pintype "passive"))
      (node (ref "JP3") (pin "5") (pinfunction "5_5") (pintype "passive"))
      (node (ref "JP3") (pin "7") (pinfunction "7_7") (pintype "passive"))
      (node (ref "JP4") (pin "10") (pinfunction "10_10") (pintype "passive"))
      (node (ref "JP4") (pin "4") (pinfunction "4_4") (pintype "passive"))
      (node (ref "JP4") (pin "6") (pinfunction "6_6") (pintype "passive"))
      (node (ref "JP4") (pin "8") (pinfunction "8_8") (pintype "passive"))
      (node (ref "JP6") (pin "10") (pinfunction "10_10") (pintype "passive"))
      (node (ref "JP9") (pin "10") (pinfunction "10_10") (pintype "passive"))
      (node (ref "JP9") (pin "4") (pinfunction "4_4") (pintype "passive"))
      (node (ref "JP9") (pin "6") (pinfunction "6_6") (pintype "passive"))
      (node (ref "JP9") (pin "8") (pinfunction "8_8") (pintype "passive"))
      (node (ref "KICKER") (pin "6") (pinfunction "6_6") (pintype "passive"))
      (node (ref "LED1") (pin "C") (pinfunction "C_C") (pintype "passive"))
      (node (ref "LINE_SISTEM") (pin "6") (pinfunction "6_6") (pintype "passive"))
      (node (ref "POWER") (pin "1") (pinfunction "1_1") (pintype "passive"))
      (node (ref "POWER") (pin "3") (pinfunction "3_3") (pintype "passive"))
      (node (ref "POWER") (pin "5") (pinfunction "5_5") (pintype "passive"))
      (node (ref "R1") (pin "1") (pinfunction "1_1") (pintype "passive"))
      (node (ref "RESET_LINE_SISTEM") (pin "3") (pinfunction "P_3") (pintype "passive"))
      (node (ref "RESET_LINE_SISTEM") (pin "4") (pinfunction "P1_4") (pintype "passive"))
      (node (ref "SMALL_LINE") (pin "6") (pinfunction "6_6") (pintype "passive"))
      (node (ref "U$4") (pin "GND") (pinfunction "GND_GND") (pintype "bidirectional"))
      (node (ref "U$4") (pin "GND_1") (pinfunction "GND_1_GND_1") (pintype "bidirectional"))
      (node (ref "U$4") (pin "GND_2") (pinfunction "GND_2_GND_2") (pintype "bidirectional"))
      (node (ref "U$4") (pin "GND_3") (pinfunction "GND_3_GND_3") (pintype "bidirectional"))
      (node (ref "U1") (pin "21") (pinfunction "AGND_21") (pintype "bidirectional"))
      (node (ref "U1") (pin "3") (pinfunction "GND_3") (pintype "bidirectional"))
      (node (ref "U1") (pin "5") (pinfunction "GND_5") (pintype "bidirectional"))
      (node (ref "U2") (pin "21") (pinfunction "AGND_21") (pintype "bidirectional"))
      (node (ref "U2") (pin "3") (pinfunction "GND_3") (pintype "bidirectional"))
      (node (ref "U2") (pin "5") (pinfunction "GND_5") (pintype "bidirectional"))
      (node (ref "ULTRA_1") (pin "4") (pinfunction "GND_4") (pintype "power_in"))
      (node (ref "ULTRA_2") (pin "4") (pinfunction "GND_4") (pintype "power_in"))
      (node (ref "ULTRA_3") (pin "4") (pinfunction "GND_4") (pintype "power_in"))
      (node (ref "ULTRA_RESET") (pin "3") (pinfunction "P_3") (pintype "passive"))
      (node (ref "ULTRA_RESET") (pin "4") (pinfunction "P1_4") (pintype "passive"))
      (node (ref "ULTRA_SISTEM") (pin "6") (pinfunction "6_6") (pintype "passive"))
    )
    (net (code "50") (name "Net-(BATERY_1-Pad3)") (class "Default")
      (node (ref "BATERY_1") (pin "3") (pinfunction "3_3") (pintype "bidirectional"))
      (node (ref "BATERY_2") (pin "5") (pinfunction "5_5") (pintype "bidirectional"))
    )
    (net (code "51") (name "Net-(BATERY_2-Pad3)") (class "Default")
      (node (ref "BATERY_2") (pin "3") (pinfunction "3_3") (pintype "bidirectional"))
      (node (ref "BATERY_3") (pin "5") (pinfunction "5_5") (pintype "bidirectional"))
    )
    (net (code "52") (name "Net-(C3-Pad2)") (class "Default")
      (node (ref "C3") (pin "2") (pinfunction "2_2") (pintype "passive"))
      (node (ref "ULTRA_SISTEM") (pin "1") (pinfunction "1_1") (pintype "passive"))
    )
    (net (code "53") (name "Net-(C14-Pad2)") (class "Default")
      (node (ref "C14") (pin "2") (pinfunction "2_2") (pintype "passive"))
      (node (ref "LINE_SISTEM") (pin "1") (pinfunction "1_1") (pintype "passive"))
    )
    (net (code "54") (name "Net-(IO1-OUT)") (class "Default")
      (node (ref "D1") (pin "K") (pinfunction "K_K") (pintype "passive"))
      (node (ref "IO1") (pin "2") (pinfunction "OUT_2") (pintype "output"))
      (node (ref "TL1") (pin "1") (pinfunction "1_1") (pintype "passive"))
    )
    (net (code "55") (name "Net-(IO2-OUT)") (class "Default")
      (node (ref "D2") (pin "K") (pinfunction "K_K") (pintype "passive"))
      (node (ref "IO2") (pin "2") (pinfunction "OUT_2") (pintype "output"))
      (node (ref "TL2") (pin "1") (pinfunction "1_1") (pintype "passive"))
    )
    (net (code "56") (name "Net-(LED1-PadA)") (class "Default")
      (node (ref "LED1") (pin "A") (pinfunction "A_A") (pintype "passive"))
      (node (ref "R5") (pin "1") (pinfunction "1_1") (pintype "passive"))
    )
    (net (code "57") (name "Net-(MAIN_POWER-2-COM)") (class "Default")
      (node (ref "FUSE") (pin "1") (pinfunction "1_1") (pintype "passive"))
      (node (ref "MAIN_POWER") (pin "2") (pinfunction "2-COM_2") (pintype "passive"))
    )
    (net (code "58") (name "Net-(RESET_LINE_SISTEM-S)") (class "Default")
      (node (ref "C14") (pin "1") (pinfunction "1_1") (pintype "passive"))
      (node (ref "R2") (pin "1") (pinfunction "1_1") (pintype "passive"))
      (node (ref "RESET_LINE_SISTEM") (pin "1") (pinfunction "S_1") (pintype "passive"))
      (node (ref "RESET_LINE_SISTEM") (pin "2") (pinfunction "S1_2") (pintype "passive"))
      (node (ref "U2") (pin "29") (pinfunction "PC6(/RESET)_29") (pintype "bidirectional"))
    )
    (net (code "59") (name "Net-(U1-PB6(XTAL1{slash}TOSC1))") (class "Default")
      (node (ref "C2") (pin "2") (pinfunction "2_2") (pintype "passive"))
      (node (ref "U1") (pin "7") (pinfunction "PB6(XTAL1/TOSC1)_7") (pintype "bidirectional"))
      (node (ref "Y1") (pin "2") (pinfunction "2_2") (pintype "passive"))
    )
    (net (code "60") (name "Net-(U1-PB7(XTAL2{slash}TOSC2))") (class "Default")
      (node (ref "C1") (pin "2") (pinfunction "2_2") (pintype "passive"))
      (node (ref "U1") (pin "8") (pinfunction "PB7(XTAL2/TOSC2)_8") (pintype "bidirectional"))
      (node (ref "Y1") (pin "1") (pinfunction "1_1") (pintype "passive"))
    )
    (net (code "61") (name "Net-(U1-PC6({slash}RESET))") (class "Default")
      (node (ref "C3") (pin "1") (pinfunction "1_1") (pintype "passive"))
      (node (ref "R8") (pin "1") (pinfunction "1_1") (pintype "passive"))
      (node (ref "U1") (pin "29") (pinfunction "PC6(/RESET)_29") (pintype "bidirectional"))
      (node (ref "ULTRA_RESET") (pin "1") (pinfunction "S_1") (pintype "passive"))
      (node (ref "ULTRA_RESET") (pin "2") (pinfunction "S1_2") (pintype "passive"))
    )
    (net (code "62") (name "Net-(U1-PD0(RXD))") (class "Default")
      (node (ref "U1") (pin "30") (pinfunction "PD0(RXD)_30") (pintype "bidirectional"))
      (node (ref "ULTRA_SISTEM") (pin "3") (pinfunction "3_3") (pintype "passive"))
    )
    (net (code "63") (name "Net-(U1-PD1(TXD))") (class "Default")
      (node (ref "U1") (pin "31") (pinfunction "PD1(TXD)_31") (pintype "bidirectional"))
      (node (ref "ULTRA_SISTEM") (pin "2") (pinfunction "2_2") (pintype "passive"))
    )
    (net (code "64") (name "Net-(U2-PB6(XTAL1{slash}TOSC1))") (class "Default")
      (node (ref "C13") (pin "2") (pinfunction "2_2") (pintype "passive"))
      (node (ref "U2") (pin "7") (pinfunction "PB6(XTAL1/TOSC1)_7") (pintype "bidirectional"))
      (node (ref "Y2") (pin "2") (pinfunction "2_2") (pintype "passive"))
    )
    (net (code "65") (name "Net-(U2-PB7(XTAL2{slash}TOSC2))") (class "Default")
      (node (ref "C12") (pin "2") (pinfunction "2_2") (pintype "passive"))
      (node (ref "U2") (pin "8") (pinfunction "PB7(XTAL2/TOSC2)_8") (pintype "bidirectional"))
      (node (ref "Y2") (pin "1") (pinfunction "1_1") (pintype "passive"))
    )
    (net (code "66") (name "unconnected-(BATERY_1-Pad1)") (class "Default")
      (node (ref "BATERY_1") (pin "1") (pinfunction "1_1") (pintype "bidirectional"))
    )
    (net (code "67") (name "unconnected-(BATERY_1-Pad2)") (class "Default")
      (node (ref "BATERY_1") (pin "2") (pinfunction "2_2") (pintype "bidirectional"))
    )
    (net (code "68") (name "unconnected-(BATERY_1-Pad4)") (class "Default")
      (node (ref "BATERY_1") (pin "4") (pinfunction "4_4") (pintype "bidirectional"))
    )
    (net (code "69") (name "unconnected-(BATERY_2-Pad1)") (class "Default")
      (node (ref "BATERY_2") (pin "1") (pinfunction "1_1") (pintype "bidirectional"))
    )
    (net (code "70") (name "unconnected-(BATERY_2-Pad2)") (class "Default")
      (node (ref "BATERY_2") (pin "2") (pinfunction "2_2") (pintype "bidirectional"))
    )
    (net (code "71") (name "unconnected-(BATERY_2-Pad4)") (class "Default")
      (node (ref "BATERY_2") (pin "4") (pinfunction "4_4") (pintype "bidirectional"))
    )
    (net (code "72") (name "unconnected-(BATERY_3-Pad1)") (class "Default")
      (node (ref "BATERY_3") (pin "1") (pinfunction "1_1") (pintype "bidirectional"))
    )
    (net (code "73") (name "unconnected-(BATERY_3-Pad2)") (class "Default")
      (node (ref "BATERY_3") (pin "2") (pinfunction "2_2") (pintype "bidirectional"))
    )
    (net (code "74") (name "unconnected-(BATERY_3-Pad4)") (class "Default")
      (node (ref "BATERY_3") (pin "4") (pinfunction "4_4") (pintype "bidirectional"))
    )
    (net (code "75") (name "unconnected-(JP8-Pad10)") (class "Default")
      (node (ref "JP8") (pin "10") (pinfunction "10_10") (pintype "passive"))
    )
    (net (code "76") (name "unconnected-(KICKER-Pad5)") (class "Default")
      (node (ref "KICKER") (pin "5") (pinfunction "5_5") (pintype "passive"))
    )
    (net (code "77") (name "unconnected-(LINE_SISTEM-Pad5)") (class "Default")
      (node (ref "LINE_SISTEM") (pin "5") (pinfunction "5_5") (pintype "passive"))
    )
    (net (code "78") (name "unconnected-(MAIN_POWER-3-ON-Pad3)") (class "Default")
      (node (ref "MAIN_POWER") (pin "3") (pinfunction "3-ON_3") (pintype "passive"))
    )
    (net (code "79") (name "unconnected-(SMALL_LINE-Pad5)") (class "Default")
      (node (ref "SMALL_LINE") (pin "5") (pinfunction "5_5") (pintype "passive"))
    )
    (net (code "80") (name "unconnected-(U$4-PadCS)") (class "Default")
      (node (ref "U$4") (pin "CS") (pinfunction "CS_CS") (pintype "bidirectional"))
    )
    (net (code "81") (name "unconnected-(U$4-PadENA{slash}DIAGA)") (class "Default")
      (node (ref "U$4") (pin "ENA/DIAGA") (pinfunction "ENA/DIAGA_ENA/DIAGA") (pintype "bidirectional"))
    )
    (net (code "82") (name "unconnected-(U$4-PadENB{slash}DIAGB)") (class "Default")
      (node (ref "U$4") (pin "ENB/DIAGB") (pinfunction "ENB/DIAGB_ENB/DIAGB") (pintype "bidirectional"))
    )
    (net (code "83") (name "unconnected-(U$4-PadVOUT)") (class "Default")
      (node (ref "U$4") (pin "VOUT") (pinfunction "VOUT_VOUT") (pintype "bidirectional"))
    )
    (net (code "84") (name "unconnected-(U1-ADC6-Pad19)") (class "Default")
      (node (ref "U1") (pin "19") (pinfunction "ADC6_19") (pintype "bidirectional"))
    )
    (net (code "85") (name "unconnected-(U1-ADC7-Pad22)") (class "Default")
      (node (ref "U1") (pin "22") (pinfunction "ADC7_22") (pintype "bidirectional"))
    )
    (net (code "86") (name "unconnected-(U1-AREF-Pad20)") (class "Default")
      (node (ref "U1") (pin "20") (pinfunction "AREF_20") (pintype "bidirectional"))
    )
    (net (code "87") (name "unconnected-(U1-PB0(ICP)-Pad12)") (class "Default")
      (node (ref "U1") (pin "12") (pinfunction "PB0(ICP)_12") (pintype "bidirectional"))
    )
    (net (code "88") (name "unconnected-(U1-PB1(OC1A)-Pad13)") (class "Default")
      (node (ref "U1") (pin "13") (pinfunction "PB1(OC1A)_13") (pintype "bidirectional"))
    )
    (net (code "89") (name "unconnected-(U1-PC0(ADC0)-Pad23)") (class "Default")
      (node (ref "U1") (pin "23") (pinfunction "PC0(ADC0)_23") (pintype "bidirectional"))
    )
    (net (code "90") (name "unconnected-(U1-PC1(ADC1)-Pad24)") (class "Default")
      (node (ref "U1") (pin "24") (pinfunction "PC1(ADC1)_24") (pintype "bidirectional"))
    )
    (net (code "91") (name "unconnected-(U1-PC2(ADC2)-Pad25)") (class "Default")
      (node (ref "U1") (pin "25") (pinfunction "PC2(ADC2)_25") (pintype "bidirectional"))
    )
    (net (code "92") (name "unconnected-(U1-PC3(ADC3)-Pad26)") (class "Default")
      (node (ref "U1") (pin "26") (pinfunction "PC3(ADC3)_26") (pintype "bidirectional"))
    )
    (net (code "93") (name "unconnected-(U1-PC4(ADC4{slash}SDA)-Pad27)") (class "Default")
      (node (ref "U1") (pin "27") (pinfunction "PC4(ADC4/SDA)_27") (pintype "bidirectional"))
    )
    (net (code "94") (name "unconnected-(U1-PC5(ADC5{slash}SCL)-Pad28)") (class "Default")
      (node (ref "U1") (pin "28") (pinfunction "PC5(ADC5/SCL)_28") (pintype "bidirectional"))
    )
    (net (code "95") (name "unconnected-(U1-PD2(INT0)-Pad32)") (class "Default")
      (node (ref "U1") (pin "32") (pinfunction "PD2(INT0)_32") (pintype "bidirectional"))
    )
    (net (code "96") (name "unconnected-(U1-PD3(INT1)-Pad1)") (class "Default")
      (node (ref "U1") (pin "1") (pinfunction "PD3(INT1)_1") (pintype "bidirectional"))
    )
    (net (code "97") (name "unconnected-(U1-PD4(XCK{slash}T0)-Pad2)") (class "Default")
      (node (ref "U1") (pin "2") (pinfunction "PD4(XCK/T0)_2") (pintype "bidirectional"))
    )
    (net (code "98") (name "unconnected-(U2-ADC6-Pad19)") (class "Default")
      (node (ref "U2") (pin "19") (pinfunction "ADC6_19") (pintype "bidirectional"))
    )
    (net (code "99") (name "unconnected-(U2-ADC7-Pad22)") (class "Default")
      (node (ref "U2") (pin "22") (pinfunction "ADC7_22") (pintype "bidirectional"))
    )
    (net (code "100") (name "unconnected-(U2-AREF-Pad20)") (class "Default")
      (node (ref "U2") (pin "20") (pinfunction "AREF_20") (pintype "bidirectional"))
    )
    (net (code "101") (name "unconnected-(U2-PC1(ADC1)-Pad24)") (class "Default")
      (node (ref "U2") (pin "24") (pinfunction "PC1(ADC1)_24") (pintype "bidirectional"))
    )
    (net (code "102") (name "unconnected-(U2-PC2(ADC2)-Pad25)") (class "Default")
      (node (ref "U2") (pin "25") (pinfunction "PC2(ADC2)_25") (pintype "bidirectional"))
    )
    (net (code "103") (name "unconnected-(U2-PC3(ADC3)-Pad26)") (class "Default")
      (node (ref "U2") (pin "26") (pinfunction "PC3(ADC3)_26") (pintype "bidirectional"))
    )
    (net (code "104") (name "unconnected-(ULTRA_SISTEM-Pad5)") (class "Default")
      (node (ref "ULTRA_SISTEM") (pin "5") (pinfunction "5_5") (pintype "passive"))
    )
  )
)
